# mini_Quad_v00.net
KiCad netlist of a schematic drawn in EAGLE
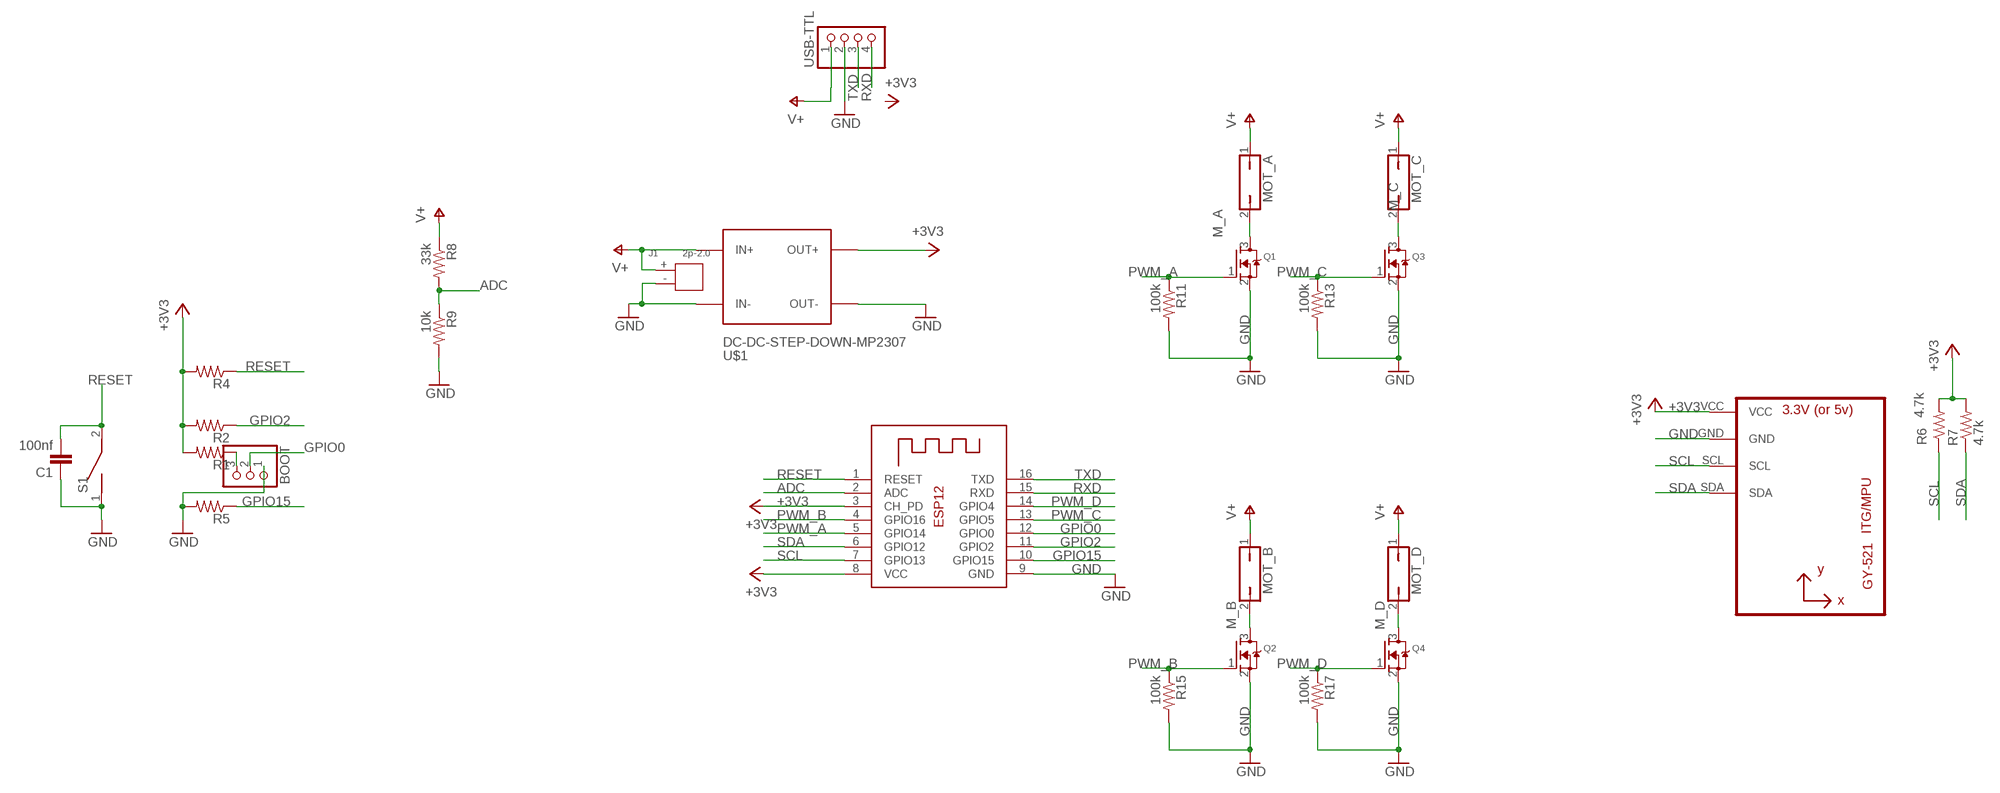
[diagram p0: schematic, sheet 1]

(export (version "E")
  (design (tool "Eeschema 10.0.6"))
  (components
    (comp (ref "BOOT")
      (value "PINHD-1X3")
      (footprint "eagle-import:1X03")
      (libsource (lib "eagle-import") (part "PINHD-1X3"))
    )
    (comp (ref "C1")
      (value "100nf")
      (footprint "eagle-import:C050-024X044")
      (libsource (lib "eagle-import") (part "C-EU050-024X044"))
    )
    (comp (ref "J1")
      (value "2p-2.0")
      (footprint "eagle-import:H2-2.0-6X4.5MM")
      (libsource (lib "eagle-import") (part "DIP-JST-2P-2.0"))
    )
    (comp (ref "MOT_A")
      (value "JP1Q")
      (footprint "eagle-import:JP1")
      (libsource (lib "eagle-import") (part "JP1Q"))
    )
    (comp (ref "MOT_B")
      (value "JP1Q")
      (footprint "eagle-import:JP1")
      (libsource (lib "eagle-import") (part "JP1Q"))
    )
    (comp (ref "MOT_C")
      (value "JP1Q")
      (footprint "eagle-import:JP1")
      (libsource (lib "eagle-import") (part "JP1Q"))
    )
    (comp (ref "MOT_D")
      (value "JP1Q")
      (footprint "eagle-import:JP1")
      (libsource (lib "eagle-import") (part "JP1Q"))
    )
    (comp (ref "Q1")
      (value "MOSFET-NTO252")
      (footprint "eagle-import:TO252")
      (libsource (lib "eagle-import") (part "MOSFET-NTO252"))
    )
    (comp (ref "Q2")
      (value "MOSFET-NTO252")
      (footprint "eagle-import:TO252")
      (libsource (lib "eagle-import") (part "MOSFET-NTO252"))
    )
    (comp (ref "Q3")
      (value "MOSFET-NTO252")
      (footprint "eagle-import:TO252")
      (libsource (lib "eagle-import") (part "MOSFET-NTO252"))
    )
    (comp (ref "Q4")
      (value "MOSFET-NTO252")
      (footprint "eagle-import:TO252")
      (libsource (lib "eagle-import") (part "MOSFET-NTO252"))
    )
    (comp (ref "R1")
      (value "R-US_0204/5")
      (footprint "eagle-import:0204_5")
      (libsource (lib "eagle-import") (part "R-US_0204/5"))
    )
    (comp (ref "R2")
      (value "R-US_0204/5")
      (footprint "eagle-import:0204_5")
      (libsource (lib "eagle-import") (part "R-US_0204/5"))
    )
    (comp (ref "R4")
      (value "R-US_0204/7")
      (footprint "eagle-import:0204_7")
      (libsource (lib "eagle-import") (part "R-US_0204/7"))
    )
    (comp (ref "R5")
      (value "R-US_0204/5")
      (footprint "eagle-import:0204_5")
      (libsource (lib "eagle-import") (part "R-US_0204/5"))
    )
    (comp (ref "R6")
      (value "4.7k")
      (footprint "eagle-import:0204_5")
      (libsource (lib "eagle-import") (part "R-US_0204/5"))
    )
    (comp (ref "R7")
      (value "4.7k")
      (footprint "eagle-import:0204_7")
      (libsource (lib "eagle-import") (part "R-US_0204/7"))
    )
    (comp (ref "R8")
      (value "33k")
      (footprint "eagle-import:0207_10")
      (libsource (lib "eagle-import") (part "R-US_0207/10"))
    )
    (comp (ref "R9")
      (value "10k")
      (footprint "eagle-import:0204_7")
      (libsource (lib "eagle-import") (part "R-US_0204/7"))
    )
    (comp (ref "R11")
      (value "100k")
      (footprint "eagle-import:0204_5")
      (libsource (lib "eagle-import") (part "R-US_0204/5"))
    )
    (comp (ref "R13")
      (value "100k")
      (footprint "eagle-import:0204_5")
      (libsource (lib "eagle-import") (part "R-US_0204/5"))
    )
    (comp (ref "R15")
      (value "100k")
      (footprint "eagle-import:0204_5")
      (libsource (lib "eagle-import") (part "R-US_0204/5"))
    )
    (comp (ref "R17")
      (value "100k")
      (footprint "eagle-import:0204_5")
      (libsource (lib "eagle-import") (part "R-US_0204/5"))
    )
    (comp (ref "S1")
      (value "DS01")
      (footprint "eagle-import:DS-01")
      (libsource (lib "eagle-import") (part "DS01"))
    )
    (comp (ref "U$1")
      (value "DC-DC-STEP-DOWN-MP2307")
      (footprint "eagle-import:DC-DC-STEP-DOWN-MP2307")
      (libsource (lib "eagle-import") (part "DC-DC-STEP-DOWN-MP2307"))
    )
    (comp (ref "U1")
      (value "GY-521MPU6050")
      (footprint "eagle-import:GY-521")
      (libsource (lib "eagle-import") (part "GY-521MPU6050"))
    )
    (comp (ref "USB-TTL")
      (value "PINHD-1X4")
      (footprint "eagle-import:1X04")
      (libsource (lib "eagle-import") (part "PINHD-1X4"))
    )
    (comp (ref "X1")
      (value "ESP-12")
      (footprint "eagle-import:ESP-12")
      (libsource (lib "eagle-import") (part "ESP-12"))
    )
  )
  (nets
    (net (code "1") (name "+3V3") (class "Default")
      (node (ref "R1") (pin "2") (pinfunction "2_2") (pintype "passive"))
      (node (ref "R2") (pin "2") (pinfunction "2_2") (pintype "passive"))
      (node (ref "R4") (pin "2") (pinfunction "2_2") (pintype "passive"))
      (node (ref "R6") (pin "2") (pinfunction "2_2") (pintype "passive"))
      (node (ref "R7") (pin "2") (pinfunction "2_2") (pintype "passive"))
      (node (ref "U$1") (pin "OUT+") (pinfunction "OUT+_OUT+") (pintype "bidirectional"))
      (node (ref "U1") (pin "VCC") (pinfunction "VCC_VCC") (pintype "bidirectional"))
      (node (ref "X1") (pin "3") (pinfunction "CH_PD_3") (pintype "input"))
      (node (ref "X1") (pin "8") (pinfunction "VCC_8") (pintype "power_in"))
    )
    (net (code "2") (name "/ADC") (class "Default")
      (node (ref "R8") (pin "2") (pinfunction "2_2") (pintype "passive"))
      (node (ref "R9") (pin "1") (pinfunction "1_1") (pintype "passive"))
      (node (ref "X1") (pin "2") (pinfunction "ADC_2") (pintype "passive"))
    )
    (net (code "3") (name "/GPIO0") (class "Default")
      (node (ref "BOOT") (pin "2") (pinfunction "2_2") (pintype "passive"))
      (node (ref "X1") (pin "12") (pinfunction "GPIO0_12") (pintype "bidirectional"))
    )
    (net (code "4") (name "/GPIO2") (class "Default")
      (node (ref "R2") (pin "1") (pinfunction "1_1") (pintype "passive"))
      (node (ref "X1") (pin "11") (pinfunction "GPIO2_11") (pintype "bidirectional"))
    )
    (net (code "5") (name "/GPIO15") (class "Default")
      (node (ref "R5") (pin "1") (pinfunction "1_1") (pintype "passive"))
      (node (ref "X1") (pin "10") (pinfunction "GPIO15_10") (pintype "bidirectional"))
    )
    (net (code "6") (name "/M_A") (class "Default")
      (node (ref "MOT_A") (pin "2") (pinfunction "2_2") (pintype "passive"))
      (node (ref "Q1") (pin "3") (pinfunction "D_3") (pintype "bidirectional"))
    )
    (net (code "7") (name "/M_B") (class "Default")
      (node (ref "MOT_B") (pin "2") (pinfunction "2_2") (pintype "passive"))
      (node (ref "Q2") (pin "3") (pinfunction "D_3") (pintype "bidirectional"))
    )
    (net (code "8") (name "/M_C") (class "Default")
      (node (ref "MOT_C") (pin "2") (pinfunction "2_2") (pintype "passive"))
      (node (ref "Q3") (pin "3") (pinfunction "D_3") (pintype "bidirectional"))
    )
    (net (code "9") (name "/M_D") (class "Default")
      (node (ref "MOT_D") (pin "2") (pinfunction "2_2") (pintype "passive"))
      (node (ref "Q4") (pin "3") (pinfunction "D_3") (pintype "bidirectional"))
    )
    (net (code "10") (name "/PWM_A") (class "Default")
      (node (ref "Q1") (pin "1") (pinfunction "G_1") (pintype "bidirectional"))
      (node (ref "R11") (pin "1") (pinfunction "1_1") (pintype "passive"))
      (node (ref "X1") (pin "5") (pinfunction "GPIO14_5") (pintype "bidirectional"))
    )
    (net (code "11") (name "/PWM_B") (class "Default")
      (node (ref "Q2") (pin "1") (pinfunction "G_1") (pintype "bidirectional"))
      (node (ref "R15") (pin "1") (pinfunction "1_1") (pintype "passive"))
      (node (ref "X1") (pin "4") (pinfunction "GPIO16_4") (pintype "bidirectional"))
    )
    (net (code "12") (name "/PWM_C") (class "Default")
      (node (ref "Q3") (pin "1") (pinfunction "G_1") (pintype "bidirectional"))
      (node (ref "R13") (pin "1") (pinfunction "1_1") (pintype "passive"))
      (node (ref "X1") (pin "13") (pinfunction "GPIO5_13") (pintype "bidirectional"))
    )
    (net (code "13") (name "/PWM_D") (class "Default")
      (node (ref "Q4") (pin "1") (pinfunction "G_1") (pintype "bidirectional"))
      (node (ref "R17") (pin "1") (pinfunction "1_1") (pintype "passive"))
      (node (ref "X1") (pin "14") (pinfunction "GPIO4_14") (pintype "bidirectional"))
    )
    (net (code "14") (name "/RESET") (class "Default")
      (node (ref "C1") (pin "2") (pinfunction "2_2") (pintype "passive"))
      (node (ref "R4") (pin "1") (pinfunction "1_1") (pintype "passive"))
      (node (ref "S1") (pin "2") (pinfunction "2_2") (pintype "passive"))
      (node (ref "X1") (pin "1") (pinfunction "RESET_1") (pintype "input"))
    )
    (net (code "15") (name "/RXD") (class "Default")
      (node (ref "USB-TTL") (pin "4") (pinfunction "4_4") (pintype "passive"))
      (node (ref "X1") (pin "15") (pinfunction "RXD_15") (pintype "input"))
    )
    (net (code "16") (name "/SCL") (class "Default")
      (node (ref "R6") (pin "1") (pinfunction "1_1") (pintype "passive"))
      (node (ref "U1") (pin "SCL") (pinfunction "SCL_SCL") (pintype "bidirectional"))
      (node (ref "X1") (pin "7") (pinfunction "GPIO13_7") (pintype "bidirectional"))
    )
    (net (code "17") (name "/SDA") (class "Default")
      (node (ref "R7") (pin "1") (pinfunction "1_1") (pintype "passive"))
      (node (ref "U1") (pin "SDA") (pinfunction "SDA_SDA") (pintype "bidirectional"))
      (node (ref "X1") (pin "6") (pinfunction "GPIO12_6") (pintype "bidirectional"))
    )
    (net (code "18") (name "/TXD") (class "Default")
      (node (ref "USB-TTL") (pin "3") (pinfunction "3_3") (pintype "passive"))
      (node (ref "X1") (pin "16") (pinfunction "TXD_16") (pintype "output"))
    )
    (net (code "19") (name "GND") (class "Default")
      (node (ref "BOOT") (pin "1") (pinfunction "1_1") (pintype "passive"))
      (node (ref "C1") (pin "1") (pinfunction "1_1") (pintype "passive"))
      (node (ref "J1") (pin "-") (pinfunction "P$2_-") (pintype "bidirectional"))
      (node (ref "Q1") (pin "2") (pinfunction "S_2") (pintype "bidirectional"))
      (node (ref "Q2") (pin "2") (pinfunction "S_2") (pintype "bidirectional"))
      (node (ref "Q3") (pin "2") (pinfunction "S_2") (pintype "bidirectional"))
      (node (ref "Q4") (pin "2") (pinfunction "S_2") (pintype "bidirectional"))
      (node (ref "R11") (pin "2") (pinfunction "2_2") (pintype "passive"))
      (node (ref "R13") (pin "2") (pinfunction "2_2") (pintype "passive"))
      (node (ref "R15") (pin "2") (pinfunction "2_2") (pintype "passive"))
      (node (ref "R17") (pin "2") (pinfunction "2_2") (pintype "passive"))
      (node (ref "R5") (pin "2") (pinfunction "2_2") (pintype "passive"))
      (node (ref "R9") (pin "2") (pinfunction "2_2") (pintype "passive"))
      (node (ref "S1") (pin "1") (pinfunction "1_1") (pintype "passive"))
      (node (ref "U$1") (pin "IN-") (pinfunction "IN-_IN-") (pintype "bidirectional"))
      (node (ref "U$1") (pin "OUT-") (pinfunction "OUT-_OUT-") (pintype "bidirectional"))
      (node (ref "U1") (pin "GND") (pinfunction "GND_GND") (pintype "bidirectional"))
      (node (ref "USB-TTL") (pin "2") (pinfunction "2_2") (pintype "passive"))
      (node (ref "X1") (pin "9") (pinfunction "GND_9") (pintype "power_in"))
    )
    (net (code "20") (name "Net-(BOOT-Pad3)") (class "Default")
      (node (ref "BOOT") (pin "3") (pinfunction "3_3") (pintype "passive"))
      (node (ref "R1") (pin "1") (pinfunction "1_1") (pintype "passive"))
    )
    (net (code "21") (name "V+") (class "Default")
      (node (ref "J1") (pin "+") (pinfunction "P$1_+") (pintype "bidirectional"))
      (node (ref "MOT_A") (pin "1") (pinfunction "1_1") (pintype "passive"))
      (node (ref "MOT_B") (pin "1") (pinfunction "1_1") (pintype "passive"))
      (node (ref "MOT_C") (pin "1") (pinfunction "1_1") (pintype "passive"))
      (node (ref "MOT_D") (pin "1") (pinfunction "1_1") (pintype "passive"))
      (node (ref "R8") (pin "1") (pinfunction "1_1") (pintype "passive"))
      (node (ref "U$1") (pin "IN+") (pinfunction "IN+_IN+") (pintype "bidirectional"))
      (node (ref "USB-TTL") (pin "1") (pinfunction "1_1") (pintype "passive"))
    )
  )
)
